# DC_POWER.net
KiCad netlist of a schematic drawn in Altium Designer
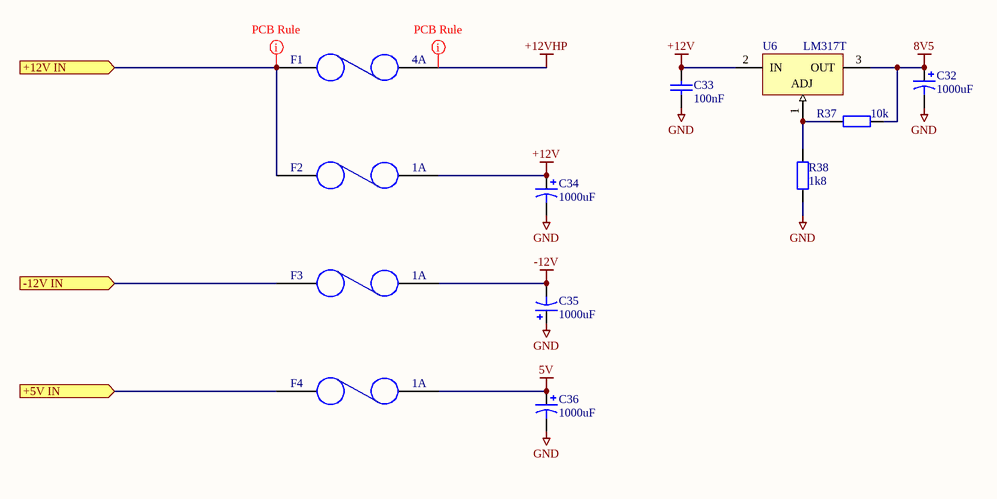
[diagram p0: DC POWER.SchDoc]

(export (version "E")
  (design (tool "Eeschema 10.0.6"))
  (components
    (comp (ref "C32")
      (value "1000uF")
      (footprint "CAPPR5-5x5")
      (description "Polarized Capacitor (Radial)")
      (fields (field (name "MANUFACTURER") "EPCOS") (field (name "MANUFACTURER PART NO.") "B41828A7107M7"))
      (libsource (lib "Miscellaneous Devices") (part "Cap Pol1"))
    )
    (comp (ref "C33")
      (value "100nF")
      (footprint "CAP (3D) - 0603")
      (description "Capacitor")
      (fields
        (field (name "MANUFACTURER") "YAEGO")
        (field (name "MANUFACTURER PART NO.") "CC0603ZRY5V9BB104")
      )
      (libsource (lib "Miscellaneous Devices") (part "Cap"))
    )
    (comp (ref "C34")
      (value "1000uF")
      (footprint "CAPPR5-5x5")
      (description "Polarized Capacitor (Radial)")
      (fields (field (name "MANUFACTURER") "EPCOS") (field (name "MANUFACTURER PART NO.") "B41828A7107M7"))
      (libsource (lib "Miscellaneous Devices") (part "Cap Pol1"))
    )
    (comp (ref "C35")
      (value "1000uF")
      (footprint "CAPPR5-5x5")
      (description "Polarized Capacitor (Radial)")
      (fields (field (name "MANUFACTURER") "EPCOS") (field (name "MANUFACTURER PART NO.") "B41828A7107M7"))
      (libsource (lib "Miscellaneous Devices") (part "Cap Pol1"))
    )
    (comp (ref "C36")
      (value "1000uF")
      (footprint "CAPPR5-5x5")
      (description "Polarized Capacitor (Radial)")
      (fields (field (name "MANUFACTURER") "EPCOS") (field (name "MANUFACTURER PART NO.") "B41828A7107M7"))
      (libsource (lib "Miscellaneous Devices") (part "Cap Pol1"))
    )
    (comp (ref "F1")
      (value "4A")
      (footprint "POLYSWITCH")
      (fields
        (field (name "MANUFACTURER") "TE CONNECTIVITY / RAYCHEM")
        (field (name "MANUFACTURER PART NO.") "RUEF400-2")
        (field (name "MOUSER PART NO.") "650-RUEF400-2")
      )
      (libsource (lib "Distribution Amp") (part "FUSE ALTRONICS S5985"))
    )
    (comp (ref "F2")
      (value "1A")
      (footprint "3216[1206]")
      (fields
        (field (name "MANUFACTURER") "TE CONNECTIVITY / RAYCHEM")
        (field (name "MANUFACTURER PART NO.") "NANOSMDC110F-2")
        (field (name "MOUSER PART NO.") "650-NANOSMDC110F-2")
      )
      (libsource (lib "Distribution Amp") (part "FUSE ALTRONICS S5985"))
    )
    (comp (ref "F3")
      (value "1A")
      (footprint "3216[1206]")
      (fields
        (field (name "MANUFACTURER") "TE CONNECTIVITY / RAYCHEM")
        (field (name "MANUFACTURER PART NO.") "NANOSMDC110F-2")
        (field (name "MOUSER PART NO.") "650-NANOSMDC110F-2")
      )
      (libsource (lib "Distribution Amp") (part "FUSE ALTRONICS S5985"))
    )
    (comp (ref "F4")
      (value "1A")
      (footprint "3216[1206]")
      (fields
        (field (name "MANUFACTURER") "TE CONNECTIVITY / RAYCHEM")
        (field (name "MANUFACTURER PART NO.") "NANOSMDC110F-2")
        (field (name "MOUSER PART NO.") "650-NANOSMDC110F-2")
      )
      (libsource (lib "Distribution Amp") (part "FUSE ALTRONICS S5985"))
    )
    (comp (ref "R37")
      (value "10k")
      (footprint "RES (3D) - 0603")
      (description "Resistor")
      (fields (field (name "MANUFACTURER") "YAEGO") (field (name "MANUFACTURER PART NO.") "AC0603JR-0710KL"))
      (libsource (lib "Miscellaneous Devices") (part "Res2"))
    )
    (comp (ref "R38")
      (value "1k8")
      (footprint "RES (3D) - 0603")
      (description "Resistor")
      (fields (field (name "MANUFACTURER") "YAEGO") (field (name "MANUFACTURER PART NO.") "AC0603FR-071K8L"))
      (libsource (lib "") (part "Res2_1"))
    )
    (comp (ref "U6")
      (value "LM317T")
      (footprint "TO220ABN")
      (description "1.2V to 37V Voltage Regulator")
      (fields (field (name "MANUFACTURER") "ON SEMI") (field (name "MANUFACTURER PART NO.") "LM317TG"))
      (libsource (lib "ST Power Mgt Voltage Regulator") (part "LM317T"))
    )
  )
  (nets
    (net (code "1") (name "+12V") (class "Default")
      (node (ref "C33") (pin "2") (pinfunction "2_2") (pintype "passive"))
      (node (ref "C34") (pin "1") (pinfunction "1_1") (pintype "passive"))
      (node (ref "F2") (pin "2") (pinfunction "2_2") (pintype "passive"))
      (node (ref "U6") (pin "2") (pinfunction "IN_2") (pintype "power_in"))
    )
    (net (code "2") (name "+12VHP") (class "Default")
      (node (ref "F1") (pin "2") (pinfunction "2_2") (pintype "passive"))
    )
    (net (code "3") (name "-12V") (class "Default")
      (node (ref "C35") (pin "2") (pinfunction "2_2") (pintype "passive"))
      (node (ref "F3") (pin "2") (pinfunction "2_2") (pintype "passive"))
    )
    (net (code "4") (name "/+5V IN") (class "Default")
      (node (ref "F4") (pin "1") (pinfunction "1_1") (pintype "passive"))
    )
    (net (code "5") (name "/+12V IN") (class "Default")
      (node (ref "F1") (pin "1") (pinfunction "1_1") (pintype "passive"))
      (node (ref "F2") (pin "1") (pinfunction "1_1") (pintype "passive"))
    )
    (net (code "6") (name "/-12V IN") (class "Default")
      (node (ref "F3") (pin "1") (pinfunction "1_1") (pintype "passive"))
    )
    (net (code "7") (name "5V") (class "Default")
      (node (ref "C36") (pin "1") (pinfunction "1_1") (pintype "passive"))
      (node (ref "F4") (pin "2") (pinfunction "2_2") (pintype "passive"))
    )
    (net (code "8") (name "8V5") (class "Default")
      (node (ref "C32") (pin "1") (pinfunction "1_1") (pintype "passive"))
      (node (ref "R37") (pin "2") (pinfunction "2_2") (pintype "passive"))
      (node (ref "U6") (pin "3") (pinfunction "OUT_3") (pintype "power_in"))
    )
    (net (code "9") (name "GND") (class "Default")
      (node (ref "C32") (pin "2") (pinfunction "2_2") (pintype "passive"))
      (node (ref "C33") (pin "1") (pinfunction "1_1") (pintype "passive"))
      (node (ref "C34") (pin "2") (pinfunction "2_2") (pintype "passive"))
      (node (ref "C35") (pin "1") (pinfunction "1_1") (pintype "passive"))
      (node (ref "C36") (pin "2") (pinfunction "2_2") (pintype "passive"))
      (node (ref "R38") (pin "1") (pinfunction "1_1") (pintype "passive"))
    )
    (net (code "10") (name "Net-(U6-ADJ)") (class "Default")
      (node (ref "R37") (pin "1") (pinfunction "1_1") (pintype "passive"))
      (node (ref "R38") (pin "2") (pinfunction "2_2") (pintype "passive"))
      (node (ref "U6") (pin "1") (pinfunction "ADJ_1") (pintype "input"))
    )
  )
)
